# AntCalc.net
KiCad netlist of a schematic drawn in EAGLE
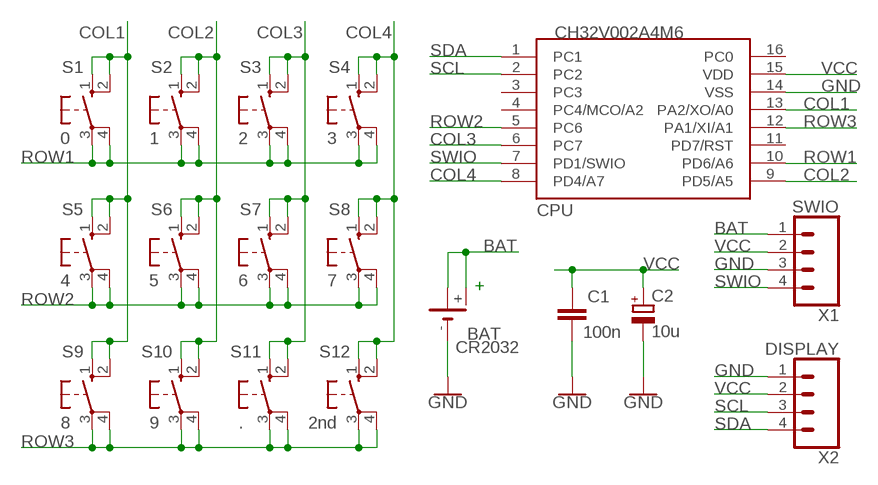
[diagram p0: schematic, sheet 1]

(export (version "E")
  (design (tool "Eeschema 10.0.6"))
  (components
    (comp (ref "BAT")
      (value "CR2032")
      (footprint "eagle-import:CR2032H")
      (libsource (lib "eagle-import") (part "CR2032H"))
    )
    (comp (ref "C1")
      (value "100n")
      (footprint "eagle-import:C0805K")
      (libsource (lib "eagle-import") (part "C-EUC0805K"))
    )
    (comp (ref "C2")
      (value "10u")
      (footprint "eagle-import:PANASONIC_B")
      (libsource (lib "eagle-import") (part "CPOL-EUB"))
    )
    (comp (ref "CPU")
      (value "CH32V002A4M6")
      (footprint "eagle-import:SOP16")
      (libsource (lib "eagle-import") (part "CH32V002A4M6"))
    )
    (comp (ref "S1")
      (value "0")
      (footprint "eagle-import:B3F-10XXC")
      (libsource (lib "eagle-import") (part "10-XXB3F-10XXC"))
    )
    (comp (ref "S2")
      (value "1")
      (footprint "eagle-import:B3F-10XXC")
      (libsource (lib "eagle-import") (part "10-XXB3F-10XXC"))
    )
    (comp (ref "S3")
      (value "2")
      (footprint "eagle-import:B3F-10XXC")
      (libsource (lib "eagle-import") (part "10-XXB3F-10XXC"))
    )
    (comp (ref "S4")
      (value "3")
      (footprint "eagle-import:B3F-10XXC")
      (libsource (lib "eagle-import") (part "10-XXB3F-10XXC"))
    )
    (comp (ref "S5")
      (value "4")
      (footprint "eagle-import:B3F-10XXC")
      (libsource (lib "eagle-import") (part "10-XXB3F-10XXC"))
    )
    (comp (ref "S6")
      (value "5")
      (footprint "eagle-import:B3F-10XXC")
      (libsource (lib "eagle-import") (part "10-XXB3F-10XXC"))
    )
    (comp (ref "S7")
      (value "6")
      (footprint "eagle-import:B3F-10XXC")
      (libsource (lib "eagle-import") (part "10-XXB3F-10XXC"))
    )
    (comp (ref "S8")
      (value "7")
      (footprint "eagle-import:B3F-10XXC")
      (libsource (lib "eagle-import") (part "10-XXB3F-10XXC"))
    )
    (comp (ref "S9")
      (value "8")
      (footprint "eagle-import:B3F-10XXC")
      (libsource (lib "eagle-import") (part "10-XXB3F-10XXC"))
    )
    (comp (ref "S10")
      (value "9")
      (footprint "eagle-import:B3F-10XXC")
      (libsource (lib "eagle-import") (part "10-XXB3F-10XXC"))
    )
    (comp (ref "S11")
      (value ".")
      (footprint "eagle-import:B3F-10XXC")
      (libsource (lib "eagle-import") (part "10-XXB3F-10XXC"))
    )
    (comp (ref "S12")
      (value "2nd")
      (footprint "eagle-import:B3F-10XXC")
      (libsource (lib "eagle-import") (part "10-XXB3F-10XXC"))
    )
    (comp (ref "X1")
      (value "SWIO")
      (footprint "eagle-import:1X04_LONGPADS")
      (libsource (lib "eagle-import") (part "CONN_04LONGPADS"))
    )
    (comp (ref "X2")
      (value "DISPLAY")
      (footprint "eagle-import:1X04")
      (libsource (lib "eagle-import") (part "CONN_04"))
    )
  )
  (nets
    (net (code "1") (name "/BAT") (class "Default")
      (node (ref "BAT") (pin "+") (pinfunction "+_+") (pintype "passive"))
      (node (ref "BAT") (pin "+@1") (pinfunction "+_+@1") (pintype "passive"))
      (node (ref "X1") (pin "1") (pinfunction "1_1") (pintype "passive"))
    )
    (net (code "2") (name "/COL1") (class "Default")
      (node (ref "CPU") (pin "13") (pinfunction "PA2/XO/A0_13") (pintype "bidirectional"))
      (node (ref "S1") (pin "1") (pinfunction "S_1") (pintype "passive"))
      (node (ref "S1") (pin "2") (pinfunction "S1_2") (pintype "passive"))
      (node (ref "S5") (pin "1") (pinfunction "S_1") (pintype "passive"))
      (node (ref "S5") (pin "2") (pinfunction "S1_2") (pintype "passive"))
      (node (ref "S9") (pin "1") (pinfunction "S_1") (pintype "passive"))
      (node (ref "S9") (pin "2") (pinfunction "S1_2") (pintype "passive"))
    )
    (net (code "3") (name "/COL2") (class "Default")
      (node (ref "CPU") (pin "9") (pinfunction "PD5/A5_9") (pintype "bidirectional"))
      (node (ref "S10") (pin "1") (pinfunction "S_1") (pintype "passive"))
      (node (ref "S10") (pin "2") (pinfunction "S1_2") (pintype "passive"))
      (node (ref "S2") (pin "1") (pinfunction "S_1") (pintype "passive"))
      (node (ref "S2") (pin "2") (pinfunction "S1_2") (pintype "passive"))
      (node (ref "S6") (pin "1") (pinfunction "S_1") (pintype "passive"))
      (node (ref "S6") (pin "2") (pinfunction "S1_2") (pintype "passive"))
    )
    (net (code "4") (name "/COL3") (class "Default")
      (node (ref "CPU") (pin "6") (pinfunction "PC7_6") (pintype "bidirectional"))
      (node (ref "S11") (pin "1") (pinfunction "S_1") (pintype "passive"))
      (node (ref "S11") (pin "2") (pinfunction "S1_2") (pintype "passive"))
      (node (ref "S3") (pin "1") (pinfunction "S_1") (pintype "passive"))
      (node (ref "S3") (pin "2") (pinfunction "S1_2") (pintype "passive"))
      (node (ref "S7") (pin "1") (pinfunction "S_1") (pintype "passive"))
      (node (ref "S7") (pin "2") (pinfunction "S1_2") (pintype "passive"))
    )
    (net (code "5") (name "/COL4") (class "Default")
      (node (ref "CPU") (pin "8") (pinfunction "PD4/A7_8") (pintype "bidirectional"))
      (node (ref "S12") (pin "1") (pinfunction "S_1") (pintype "passive"))
      (node (ref "S12") (pin "2") (pinfunction "S1_2") (pintype "passive"))
      (node (ref "S4") (pin "1") (pinfunction "S_1") (pintype "passive"))
      (node (ref "S4") (pin "2") (pinfunction "S1_2") (pintype "passive"))
      (node (ref "S8") (pin "1") (pinfunction "S_1") (pintype "passive"))
      (node (ref "S8") (pin "2") (pinfunction "S1_2") (pintype "passive"))
    )
    (net (code "6") (name "/ROW1") (class "Default")
      (node (ref "CPU") (pin "10") (pinfunction "PD6/A6_10") (pintype "bidirectional"))
      (node (ref "S1") (pin "3") (pinfunction "P_3") (pintype "passive"))
      (node (ref "S1") (pin "4") (pinfunction "P1_4") (pintype "passive"))
      (node (ref "S2") (pin "3") (pinfunction "P_3") (pintype "passive"))
      (node (ref "S2") (pin "4") (pinfunction "P1_4") (pintype "passive"))
      (node (ref "S3") (pin "3") (pinfunction "P_3") (pintype "passive"))
      (node (ref "S3") (pin "4") (pinfunction "P1_4") (pintype "passive"))
      (node (ref "S4") (pin "3") (pinfunction "P_3") (pintype "passive"))
      (node (ref "S4") (pin "4") (pinfunction "P1_4") (pintype "passive"))
    )
    (net (code "7") (name "/ROW2") (class "Default")
      (node (ref "CPU") (pin "5") (pinfunction "PC6_5") (pintype "bidirectional"))
      (node (ref "S5") (pin "3") (pinfunction "P_3") (pintype "passive"))
      (node (ref "S5") (pin "4") (pinfunction "P1_4") (pintype "passive"))
      (node (ref "S6") (pin "3") (pinfunction "P_3") (pintype "passive"))
      (node (ref "S6") (pin "4") (pinfunction "P1_4") (pintype "passive"))
      (node (ref "S7") (pin "3") (pinfunction "P_3") (pintype "passive"))
      (node (ref "S7") (pin "4") (pinfunction "P1_4") (pintype "passive"))
      (node (ref "S8") (pin "3") (pinfunction "P_3") (pintype "passive"))
      (node (ref "S8") (pin "4") (pinfunction "P1_4") (pintype "passive"))
    )
    (net (code "8") (name "/ROW3") (class "Default")
      (node (ref "CPU") (pin "12") (pinfunction "PA1/XI/A1_12") (pintype "bidirectional"))
      (node (ref "S10") (pin "3") (pinfunction "P_3") (pintype "passive"))
      (node (ref "S10") (pin "4") (pinfunction "P1_4") (pintype "passive"))
      (node (ref "S11") (pin "3") (pinfunction "P_3") (pintype "passive"))
      (node (ref "S11") (pin "4") (pinfunction "P1_4") (pintype "passive"))
      (node (ref "S12") (pin "3") (pinfunction "P_3") (pintype "passive"))
      (node (ref "S12") (pin "4") (pinfunction "P1_4") (pintype "passive"))
      (node (ref "S9") (pin "3") (pinfunction "P_3") (pintype "passive"))
      (node (ref "S9") (pin "4") (pinfunction "P1_4") (pintype "passive"))
    )
    (net (code "9") (name "/SCL") (class "Default")
      (node (ref "CPU") (pin "2") (pinfunction "PC2_2") (pintype "bidirectional"))
      (node (ref "X2") (pin "3") (pinfunction "3_3") (pintype "passive"))
    )
    (net (code "10") (name "/SDA") (class "Default")
      (node (ref "CPU") (pin "1") (pinfunction "PC1_1") (pintype "bidirectional"))
      (node (ref "X2") (pin "4") (pinfunction "4_4") (pintype "passive"))
    )
    (net (code "11") (name "/SWIO") (class "Default")
      (node (ref "CPU") (pin "7") (pinfunction "PD1/SWIO_7") (pintype "bidirectional"))
      (node (ref "X1") (pin "4") (pinfunction "4_4") (pintype "passive"))
    )
    (net (code "12") (name "/VCC") (class "Default")
      (node (ref "C1") (pin "1") (pinfunction "1_1") (pintype "passive"))
      (node (ref "C2") (pin "+") (pinfunction "+_+") (pintype "passive"))
      (node (ref "CPU") (pin "15") (pinfunction "VDD_15") (pintype "power_in"))
      (node (ref "X1") (pin "2") (pinfunction "2_2") (pintype "passive"))
      (node (ref "X2") (pin "2") (pinfunction "2_2") (pintype "passive"))
    )
    (net (code "13") (name "GND") (class "Default")
      (node (ref "BAT") (pin "-") (pinfunction "-_-") (pintype "passive"))
      (node (ref "C1") (pin "2") (pinfunction "2_2") (pintype "passive"))
      (node (ref "C2") (pin "-") (pinfunction "-_-") (pintype "passive"))
      (node (ref "CPU") (pin "14") (pinfunction "VSS_14") (pintype "power_in"))
      (node (ref "X1") (pin "3") (pinfunction "3_3") (pintype "passive"))
      (node (ref "X2") (pin "1") (pinfunction "1_1") (pintype "passive"))
    )
    (net (code "14") (name "unconnected-(CPU-PC0-Pad16)") (class "Default")
      (node (ref "CPU") (pin "16") (pinfunction "PC0_16") (pintype "bidirectional"))
    )
    (net (code "15") (name "unconnected-(CPU-PC3-Pad3)") (class "Default")
      (node (ref "CPU") (pin "3") (pinfunction "PC3_3") (pintype "bidirectional"))
    )
    (net (code "16") (name "unconnected-(CPU-PC4{slash}MCO{slash}A2-Pad4)") (class "Default")
      (node (ref "CPU") (pin "4") (pinfunction "PC4/MCO/A2_4") (pintype "bidirectional"))
    )
    (net (code "17") (name "unconnected-(CPU-PD7{slash}RST-Pad11)") (class "Default")
      (node (ref "CPU") (pin "11") (pinfunction "PD7/RST_11") (pintype "bidirectional"))
    )
  )
)
